# MCU.net
KiCad netlist of a schematic drawn in Altium Designer
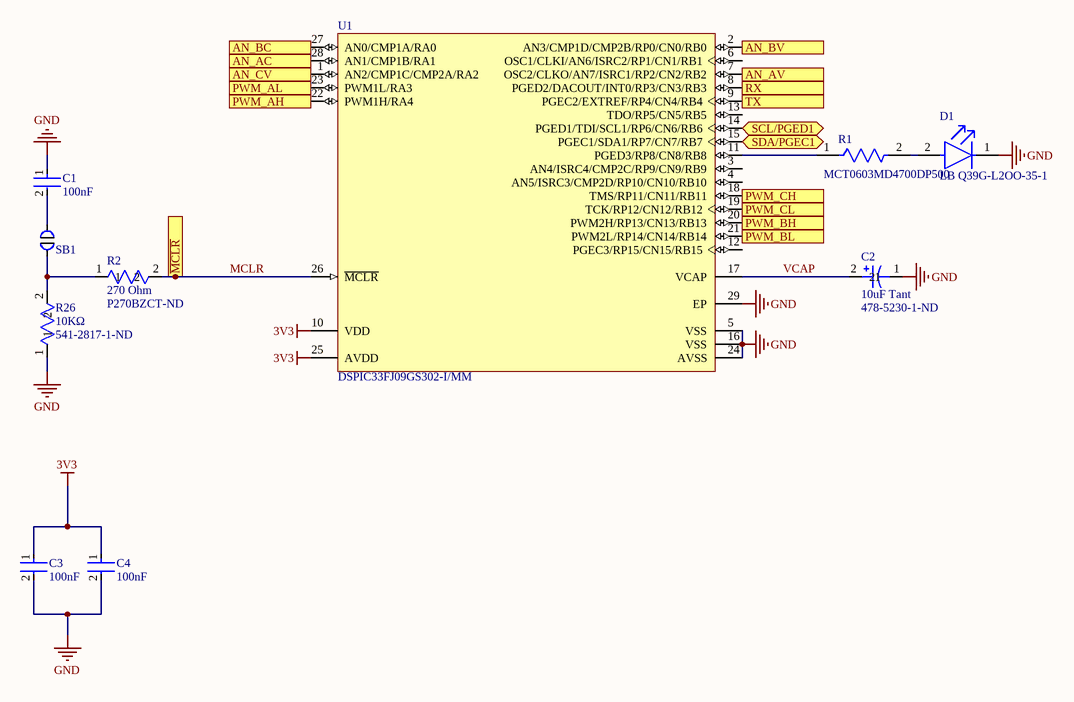
[diagram p0: MCU.SchDoc]

(export (version "E")
  (design (tool "Eeschema 10.0.6"))
  (components
    (comp (ref "C1")
      (value "100nF")
      (footprint "FP-CL10-IPC_C")
      (description "Cap Ceramic 100nF 50V X7R ±20% Pad SMD 0603 +125°C T/R")
      (fields (field (name "TOLERANCE") "20%"))
      (libsource (lib "Altium Content Vault") (part "b4654b650e69147ec39a6b967a45e02"))
    )
    (comp (ref "C2")
      (value "10uF Tant")
      (footprint "TPSB106K016R0500")
      (description "CAP TANT 10UF 10% 16V SMD")
      (fields
        (field (name "MANUFACTURER") "Kyocera AVX")
        (field (name "MANUFACTURER PART NUMBER") "TPSB106K016R0500")
        (field (name "SUPPLIER PART NUMBER 1") "478-5230-1-ND")
      )
      (libsource (lib "Schematic Library") (part "TPSB106K016R0500"))
    )
    (comp (ref "C3")
      (value "100nF")
      (footprint "FP-CL10-IPC_C")
      (description "Cap Ceramic 100nF 50V X7R ±20% Pad SMD 0603 +125°C T/R")
      (fields (field (name "TOLERANCE") "20%"))
      (libsource (lib "Altium Content Vault") (part "b4654b650e69147ec39a6b967a45e02"))
    )
    (comp (ref "C4")
      (value "100nF")
      (footprint "FP-CL10-IPC_C")
      (description "Cap Ceramic 100nF 50V X7R ±20% Pad SMD 0603 +125°C T/R")
      (fields (field (name "TOLERANCE") "20%"))
      (libsource (lib "Altium Content Vault") (part "b4654b650e69147ec39a6b967a45e02"))
    )
    (comp (ref "D1")
      (value "LB Q39G-L2OO-35-1")
      (footprint "FP-LB_Q39G-MFG")
      (description "LED BLUE DIFFUSED 0603 SMD")
      (libsource (lib "Altium Content Vault") (part "8706943c75ba83719d021d2fdc84c58"))
    )
    (comp (ref "R1")
      (value "MCT0603MD4700DP500")
      (footprint "FP-MCT0603-IPC_A")
      (description "RES SMD 100 OHM 1% 1/8W 0603")
      (fields (field (name "TOLERANCE") "0.5%"))
      (libsource (lib "Altium Content Vault") (part "1029c3af85768c4190bb7ad29bc67b5"))
    )
    (comp (ref "R2")
      (value "270 Ohm")
      (footprint "ERJ-PA3J271V")
      (description "Res Thick Film 0603 270 Ohm 5% 0.25W(1/4W) ±200ppm/C Pad SMD Automotive T/R")
      (fields
        (field (name "MANUFACTURER") "Panasonic")
        (field (name "MANUFACTURER PART NUMBER") "ERJ-PA3J271V")
        (field (name "SUPPLIER PART NUMBER 1") "P270BZCT-ND")
      )
      (libsource (lib "Schematic Library") (part "ERJ-PA3J271V"))
    )
    (comp (ref "R26")
      (value "10KΩ")
      (footprint "RCS060310K0JNEA")
      (description "RES SMD 10K OHM 5% 1/4W 0603")
      (fields
        (field (name "MANUFACTURER") "Vishay Dale")
        (field (name "MANUFACTURER PART NUMBER") "RCS060310K0JNEA")
        (field (name "SUPPLIER PART NUMBER 1") "541-2817-1-ND")
      )
      (libsource (lib "Schematic Library") (part "RCS060310K0JNEA"))
    )
    (comp (ref "SB1")
      (value "Solder Bridge Open")
      (footprint "Solder Bridge Open")
      (libsource (lib "Schematic Library") (part "Solder Bridge Open"))
    )
    (comp (ref "U1")
      (value "DSPIC33FJ09GS302-I/MM")
      (footprint "MCHP-QFN-S-MM28_M")
      (fields (field (name "MANUFACTURER") "Microchip"))
      (libsource (lib "Altium Content Vault") (part "MCHP-dsPIC33FJ09GS302-QFN-S-28"))
    )
  )
  (nets
    (net (code "1") (name "/AN_AC") (class "Default")
      (node (ref "U1") (pin "28") (pinfunction "AN1/CMP1B/RA1_28") (pintype "bidirectional"))
    )
    (net (code "2") (name "/AN_AV") (class "Default")
      (node (ref "U1") (pin "7") (pinfunction "OSC2/CLKO/AN7/ISRC1/RP2/CN2/RB2_7") (pintype "bidirectional"))
    )
    (net (code "3") (name "/AN_BC") (class "Default")
      (node (ref "U1") (pin "27") (pinfunction "AN0/CMP1A/RA0_27") (pintype "bidirectional"))
    )
    (net (code "4") (name "/AN_BV") (class "Default")
      (node (ref "U1") (pin "2") (pinfunction "AN3/CMP1D/CMP2B/RP0/CN0/RB0_2") (pintype "bidirectional"))
    )
    (net (code "5") (name "/AN_CV") (class "Default")
      (node (ref "U1") (pin "1") (pinfunction "AN2/CMP1C/CMP2A/RA2_1") (pintype "bidirectional"))
    )
    (net (code "6") (name "/MCLR") (class "Default")
      (node (ref "R2") (pin "2") (pinfunction "2_2") (pintype "passive"))
      (node (ref "U1") (pin "26") (pinfunction "~{MCLR}_26") (pintype "input"))
    )
    (net (code "7") (name "/PWM_AH") (class "Default")
      (node (ref "U1") (pin "22") (pinfunction "PWM1H/RA4_22") (pintype "bidirectional"))
    )
    (net (code "8") (name "/PWM_AL") (class "Default")
      (node (ref "U1") (pin "23") (pinfunction "PWM1L/RA3_23") (pintype "bidirectional"))
    )
    (net (code "9") (name "/PWM_BH") (class "Default")
      (node (ref "U1") (pin "20") (pinfunction "PWM2H/RP13/CN13/RB13_20") (pintype "bidirectional"))
    )
    (net (code "10") (name "/PWM_BL") (class "Default")
      (node (ref "U1") (pin "21") (pinfunction "PWM2L/RP14/CN14/RB14_21") (pintype "bidirectional"))
    )
    (net (code "11") (name "/PWM_CH") (class "Default")
      (node (ref "U1") (pin "18") (pinfunction "TMS/RP11/CN11/RB11_18") (pintype "bidirectional"))
    )
    (net (code "12") (name "/PWM_CL") (class "Default")
      (node (ref "U1") (pin "19") (pinfunction "TCK/RP12/CN12/RB12_19") (pintype "bidirectional"))
    )
    (net (code "13") (name "/RX") (class "Default")
      (node (ref "U1") (pin "8") (pinfunction "PGED2/DACOUT/INT0/RP3/CN3/RB3_8") (pintype "bidirectional"))
    )
    (net (code "14") (name "/SCL{slash}PGED1") (class "Default")
      (node (ref "U1") (pin "14") (pinfunction "PGED1/TDI/SCL1/RP6/CN6/RB6_14") (pintype "bidirectional"))
    )
    (net (code "15") (name "/SDA{slash}PGEC1") (class "Default")
      (node (ref "U1") (pin "15") (pinfunction "PGEC1/SDA1/RP7/CN7/RB7_15") (pintype "bidirectional"))
    )
    (net (code "16") (name "/TX") (class "Default")
      (node (ref "U1") (pin "9") (pinfunction "PGEC2/EXTREF/RP4/CN4/RB4_9") (pintype "bidirectional"))
    )
    (net (code "17") (name "/VCAP") (class "Default")
      (node (ref "C2") (pin "2") (pinfunction "2_2") (pintype "passive"))
      (node (ref "U1") (pin "17") (pinfunction "VCAP_17") (pintype "passive"))
    )
    (net (code "18") (name "3V3") (class "Default")
      (node (ref "C3") (pin "1") (pinfunction "1_1") (pintype "passive"))
      (node (ref "C4") (pin "1") (pinfunction "1_1") (pintype "passive"))
      (node (ref "U1") (pin "10") (pinfunction "VDD_10") (pintype "power_in"))
      (node (ref "U1") (pin "25") (pinfunction "AVDD_25") (pintype "power_in"))
    )
    (net (code "19") (name "GND") (class "Default")
      (node (ref "C1") (pin "1") (pinfunction "1_1") (pintype "passive"))
      (node (ref "C2") (pin "1") (pinfunction "1_1") (pintype "passive"))
      (node (ref "C3") (pin "2") (pinfunction "2_2") (pintype "passive"))
      (node (ref "C4") (pin "2") (pinfunction "2_2") (pintype "passive"))
      (node (ref "D1") (pin "1") (pinfunction "C_1") (pintype "passive"))
      (node (ref "R26") (pin "1") (pinfunction "1_1") (pintype "passive"))
      (node (ref "U1") (pin "16") (pinfunction "VSS_16") (pintype "power_in"))
      (node (ref "U1") (pin "24") (pinfunction "AVSS_24") (pintype "power_in"))
      (node (ref "U1") (pin "29") (pinfunction "EP_29") (pintype "power_in"))
      (node (ref "U1") (pin "5") (pinfunction "VSS_5") (pintype "power_in"))
    )
    (net (code "20") (name "Net-(D1-A)") (class "Default")
      (node (ref "D1") (pin "2") (pinfunction "A_2") (pintype "passive"))
      (node (ref "R1") (pin "2") (pinfunction "2_2") (pintype "passive"))
    )
    (net (code "21") (name "Net-(SB1-0)") (class "Default")
      (node (ref "C1") (pin "2") (pinfunction "2_2") (pintype "passive"))
      (node (ref "SB1") (pin "1") (pinfunction "0_1") (pintype "passive"))
    )
    (net (code "22") (name "Net-(SB1-1)") (class "Default")
      (node (ref "R2") (pin "1") (pinfunction "1_1") (pintype "passive"))
      (node (ref "R26") (pin "2") (pinfunction "2_2") (pintype "passive"))
      (node (ref "SB1") (pin "2") (pinfunction "1_2") (pintype "passive"))
    )
    (net (code "23") (name "Net-(U1-PGED3{slash}RP8{slash}CN8{slash}RB8)") (class "Default")
      (node (ref "R1") (pin "1") (pinfunction "1_1") (pintype "passive"))
      (node (ref "U1") (pin "11") (pinfunction "PGED3/RP8/CN8/RB8_11") (pintype "bidirectional"))
    )
    (net (code "24") (name "unconnected-(U1-AN4{slash}ISRC4{slash}CMP2C{slash}RP9{slash}CN9{slash}RB9-Pad3)") (class "Default")
      (node (ref "U1") (pin "3") (pinfunction "AN4/ISRC4/CMP2C/RP9/CN9/RB9_3") (pintype "bidirectional"))
    )
    (net (code "25") (name "unconnected-(U1-AN5{slash}ISRC3{slash}CMP2D{slash}RP10{slash}CN10{slash}RB10-Pad4)") (class "Default")
      (node (ref "U1") (pin "4") (pinfunction "AN5/ISRC3/CMP2D/RP10/CN10/RB10_4") (pintype "bidirectional"))
    )
    (net (code "26") (name "unconnected-(U1-OSC1{slash}CLKI{slash}AN6{slash}ISRC2{slash}RP1{slash}CN1{slash}RB1-Pad6)") (class "Default")
      (node (ref "U1") (pin "6") (pinfunction "OSC1/CLKI/AN6/ISRC2/RP1/CN1/RB1_6") (pintype "bidirectional"))
    )
    (net (code "27") (name "unconnected-(U1-PGEC3{slash}RP15{slash}CN15{slash}RB15-Pad12)") (class "Default")
      (node (ref "U1") (pin "12") (pinfunction "PGEC3/RP15/CN15/RB15_12") (pintype "bidirectional"))
    )
    (net (code "28") (name "unconnected-(U1-TDO{slash}RP5{slash}CN5{slash}RB5-Pad13)") (class "Default")
      (node (ref "U1") (pin "13") (pinfunction "TDO/RP5/CN5/RB5_13") (pintype "bidirectional"))
    )
  )
)
